# POWER_RAIL_CTRL.net
KiCad netlist of a schematic drawn in Altium Designer
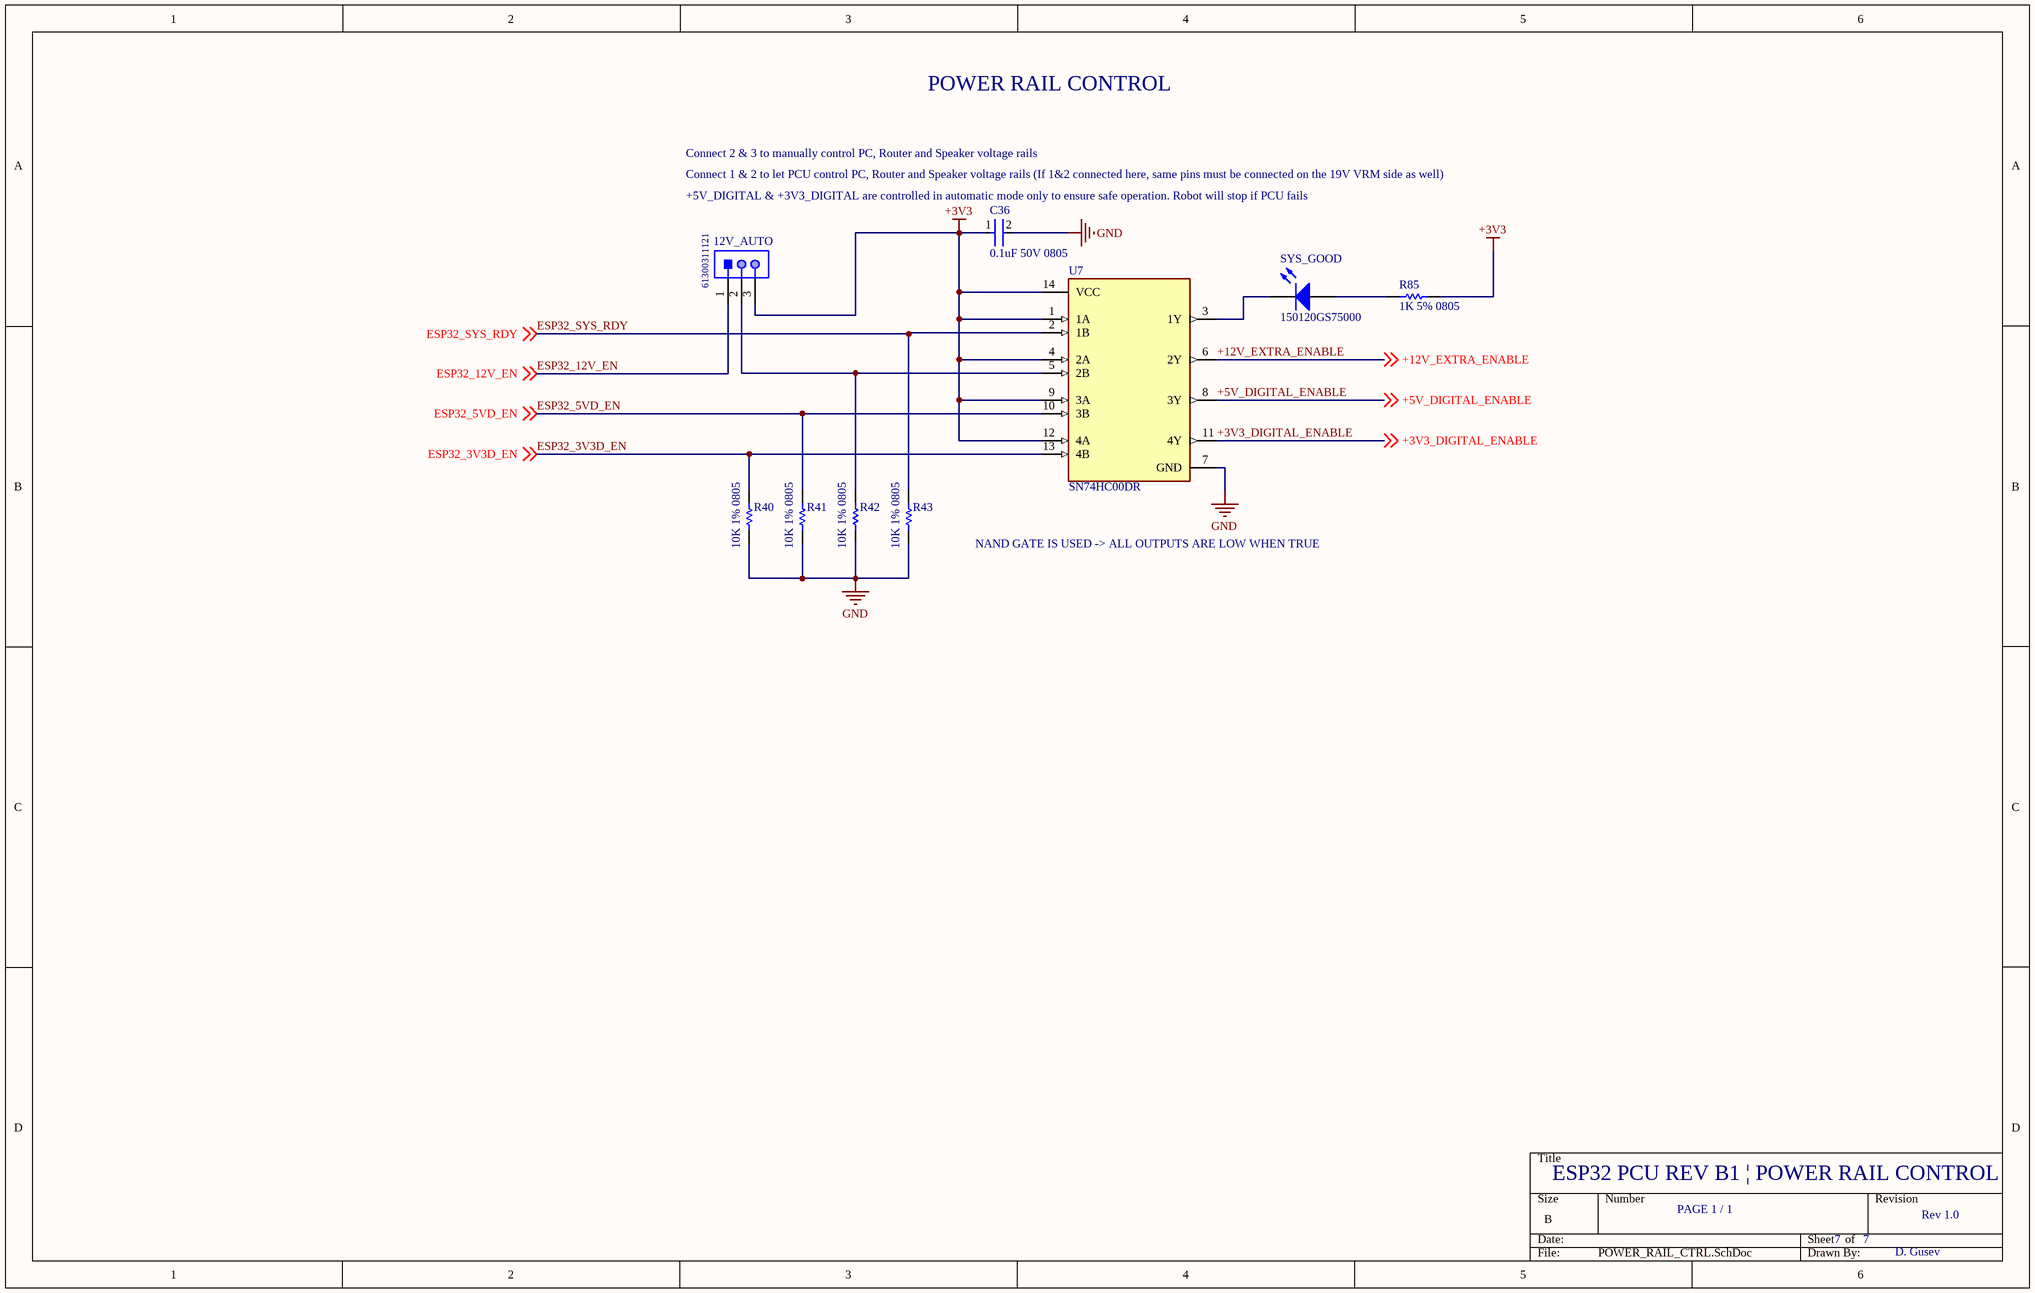
[diagram p0: POWER_RAIL_CTRL.SchDoc]

(export (version "E")
  (design (tool "Eeschema 10.0.6"))
  (components
    (comp (ref "12V_AUTO")
      (value "61300311121")
      (footprint "61300311121")
      (description "THT Vertical Pin Header WR-PHD, Pitch 2.54 mm, Single Row, 3 pins")
      (fields (field (name "MANUFACTURER") "Wurth Elektronik") (field (name "PUBLISHER") "WurthElektronik"))
      (libsource (lib "Altium Content Vault") (part "WE-CN-1P-M-R3"))
    )
    (comp (ref "C36")
      (value "0.1uF 50V 0805")
      (footprint "FP-C0805C-DN-MFG")
      (description "CAP CER 0.1UF 50V X7R 0805")
      (fields
        (field (name "MANUFACTURER PART NUMBER") "C0805C104K5RACTU")
        (field (name "MANUFACTURER") "KEMET")
      )
      (libsource (lib "Altium Content Vault") (part "b4654b650e69147ec39a6b967a45e02"))
    )
    (comp (ref "R40")
      (value "10K 1% 0805")
      (footprint "RESC2013X60X35NL10T20")
      (description "Chip Resistor, 10 KOhm, +/- 1%, 0.125 W, -55 to 155 degC, 0805 (2012 Metric), RoHS, Tape and Reel")
      (fields (field (name "MANUFACTURER") "Yageo"))
      (libsource (lib "Altium Content Vault") (part "RES-2"))
    )
    (comp (ref "R41")
      (value "10K 1% 0805")
      (footprint "RESC2013X60X35NL10T20")
      (description "Chip Resistor, 10 KOhm, +/- 1%, 0.125 W, -55 to 155 degC, 0805 (2012 Metric), RoHS, Tape and Reel")
      (fields (field (name "MANUFACTURER") "Yageo"))
      (libsource (lib "Altium Content Vault") (part "RES-2"))
    )
    (comp (ref "R42")
      (value "10K 1% 0805")
      (footprint "RESC2013X60X35NL10T20")
      (description "Chip Resistor, 10 KOhm, +/- 1%, 0.125 W, -55 to 155 degC, 0805 (2012 Metric), RoHS, Tape and Reel")
      (fields (field (name "MANUFACTURER") "Yageo"))
      (libsource (lib "Altium Content Vault") (part "RES-2"))
    )
    (comp (ref "R43")
      (value "10K 1% 0805")
      (footprint "RESC2013X60X35NL10T20")
      (description "Chip Resistor, 10 KOhm, +/- 1%, 0.125 W, -55 to 155 degC, 0805 (2012 Metric), RoHS, Tape and Reel")
      (fields (field (name "MANUFACTURER") "Yageo"))
      (libsource (lib "Altium Content Vault") (part "RES-2"))
    )
    (comp (ref "R85")
      (value "1K 5% 0805")
      (footprint "RESC2013X60X40ML20T25")
      (fields (field (name "PART NUMBER") "ERA6AEB123V") (field (name "MANUFACTURER") "Panasonic"))
      (libsource (lib "Altium Content Vault") (part "RES"))
    )
    (comp (ref "SYS_GOOD")
      (value "150120GS75000")
      (footprint "1206_A")
      (description "SMD mono-color Chip LED, WL-SMCW, Green")
      (fields (field (name "MANUFACTURER") "Wuerth Elektronik"))
      (libsource (lib "Altium Content Vault") (part "WE-LED_K1A2-2"))
    )
    (comp (ref "U7")
      (value "SN74HC00DR")
      (footprint "FP-D0014A-MFG")
      (description "IC GATE NAND 4CH 2-INP 14SOIC")
      (libsource (lib "Altium Content Vault") (part "2c7ba7b3eb294338d27c07afa77b609"))
    )
  )
  (nets
    (net (code "1") (name "+3V3") (class "Default")
      (node (ref "12V_AUTO") (pin "3") (pinfunction "3_3") (pintype "passive"))
      (node (ref "C36") (pin "1") (pinfunction "1_1") (pintype "passive"))
      (node (ref "R85") (pin "1") (pinfunction "1_1") (pintype "passive"))
      (node (ref "U7") (pin "1") (pinfunction "1A_1") (pintype "input"))
      (node (ref "U7") (pin "12") (pinfunction "4A_12") (pintype "input"))
      (node (ref "U7") (pin "14") (pinfunction "VCC_14") (pintype "power_in"))
      (node (ref "U7") (pin "4") (pinfunction "2A_4") (pintype "input"))
      (node (ref "U7") (pin "9") (pinfunction "3A_9") (pintype "input"))
    )
    (net (code "2") (name "+3V3_DIGITAL_ENABLE") (class "Default")
      (node (ref "U7") (pin "11") (pinfunction "4Y_11") (pintype "output"))
    )
    (net (code "3") (name "+5V_DIGITAL_ENABLE") (class "Default")
      (node (ref "U7") (pin "8") (pinfunction "3Y_8") (pintype "output"))
    )
    (net (code "4") (name "+12V_EXTRA_ENABLE") (class "Default")
      (node (ref "U7") (pin "6") (pinfunction "2Y_6") (pintype "output"))
    )
    (net (code "5") (name "ESP32_3V3D_EN") (class "Default")
      (node (ref "R40") (pin "2") (pinfunction "2_2") (pintype "passive"))
      (node (ref "U7") (pin "13") (pinfunction "4B_13") (pintype "input"))
    )
    (net (code "6") (name "ESP32_5VD_EN") (class "Default")
      (node (ref "R41") (pin "2") (pinfunction "2_2") (pintype "passive"))
      (node (ref "U7") (pin "10") (pinfunction "3B_10") (pintype "input"))
    )
    (net (code "7") (name "ESP32_12V_EN") (class "Default")
      (node (ref "12V_AUTO") (pin "1") (pinfunction "1_1") (pintype "passive"))
    )
    (net (code "8") (name "ESP32_SYS_RDY") (class "Default")
      (node (ref "R43") (pin "2") (pinfunction "2_2") (pintype "passive"))
      (node (ref "U7") (pin "2") (pinfunction "1B_2") (pintype "input"))
    )
    (net (code "9") (name "GND") (class "Default")
      (node (ref "C36") (pin "2") (pinfunction "2_2") (pintype "passive"))
      (node (ref "R40") (pin "1") (pinfunction "1_1") (pintype "passive"))
      (node (ref "R41") (pin "1") (pinfunction "1_1") (pintype "passive"))
      (node (ref "R42") (pin "1") (pinfunction "1_1") (pintype "passive"))
      (node (ref "R43") (pin "1") (pinfunction "1_1") (pintype "passive"))
      (node (ref "U7") (pin "7") (pinfunction "GND_7") (pintype "power_in"))
    )
    (net (code "10") (name "Net-(SYS_GOOD-A)") (class "Default")
      (node (ref "R85") (pin "2") (pinfunction "2_2") (pintype "passive"))
      (node (ref "SYS_GOOD") (pin "2") (pinfunction "A_2") (pintype "passive"))
    )
    (net (code "11") (name "Net-(SYS_GOOD-K)") (class "Default")
      (node (ref "SYS_GOOD") (pin "1") (pinfunction "K_1") (pintype "passive"))
      (node (ref "U7") (pin "3") (pinfunction "1Y_3") (pintype "output"))
    )
    (net (code "12") (name "Net-(U7-2B)") (class "Default")
      (node (ref "12V_AUTO") (pin "2") (pinfunction "2_2") (pintype "passive"))
      (node (ref "R42") (pin "2") (pinfunction "2_2") (pintype "passive"))
      (node (ref "U7") (pin "5") (pinfunction "2B_5") (pintype "input"))
    )
  )
)
